# slider_V01.net
KiCad netlist of a schematic drawn in Altium Designer
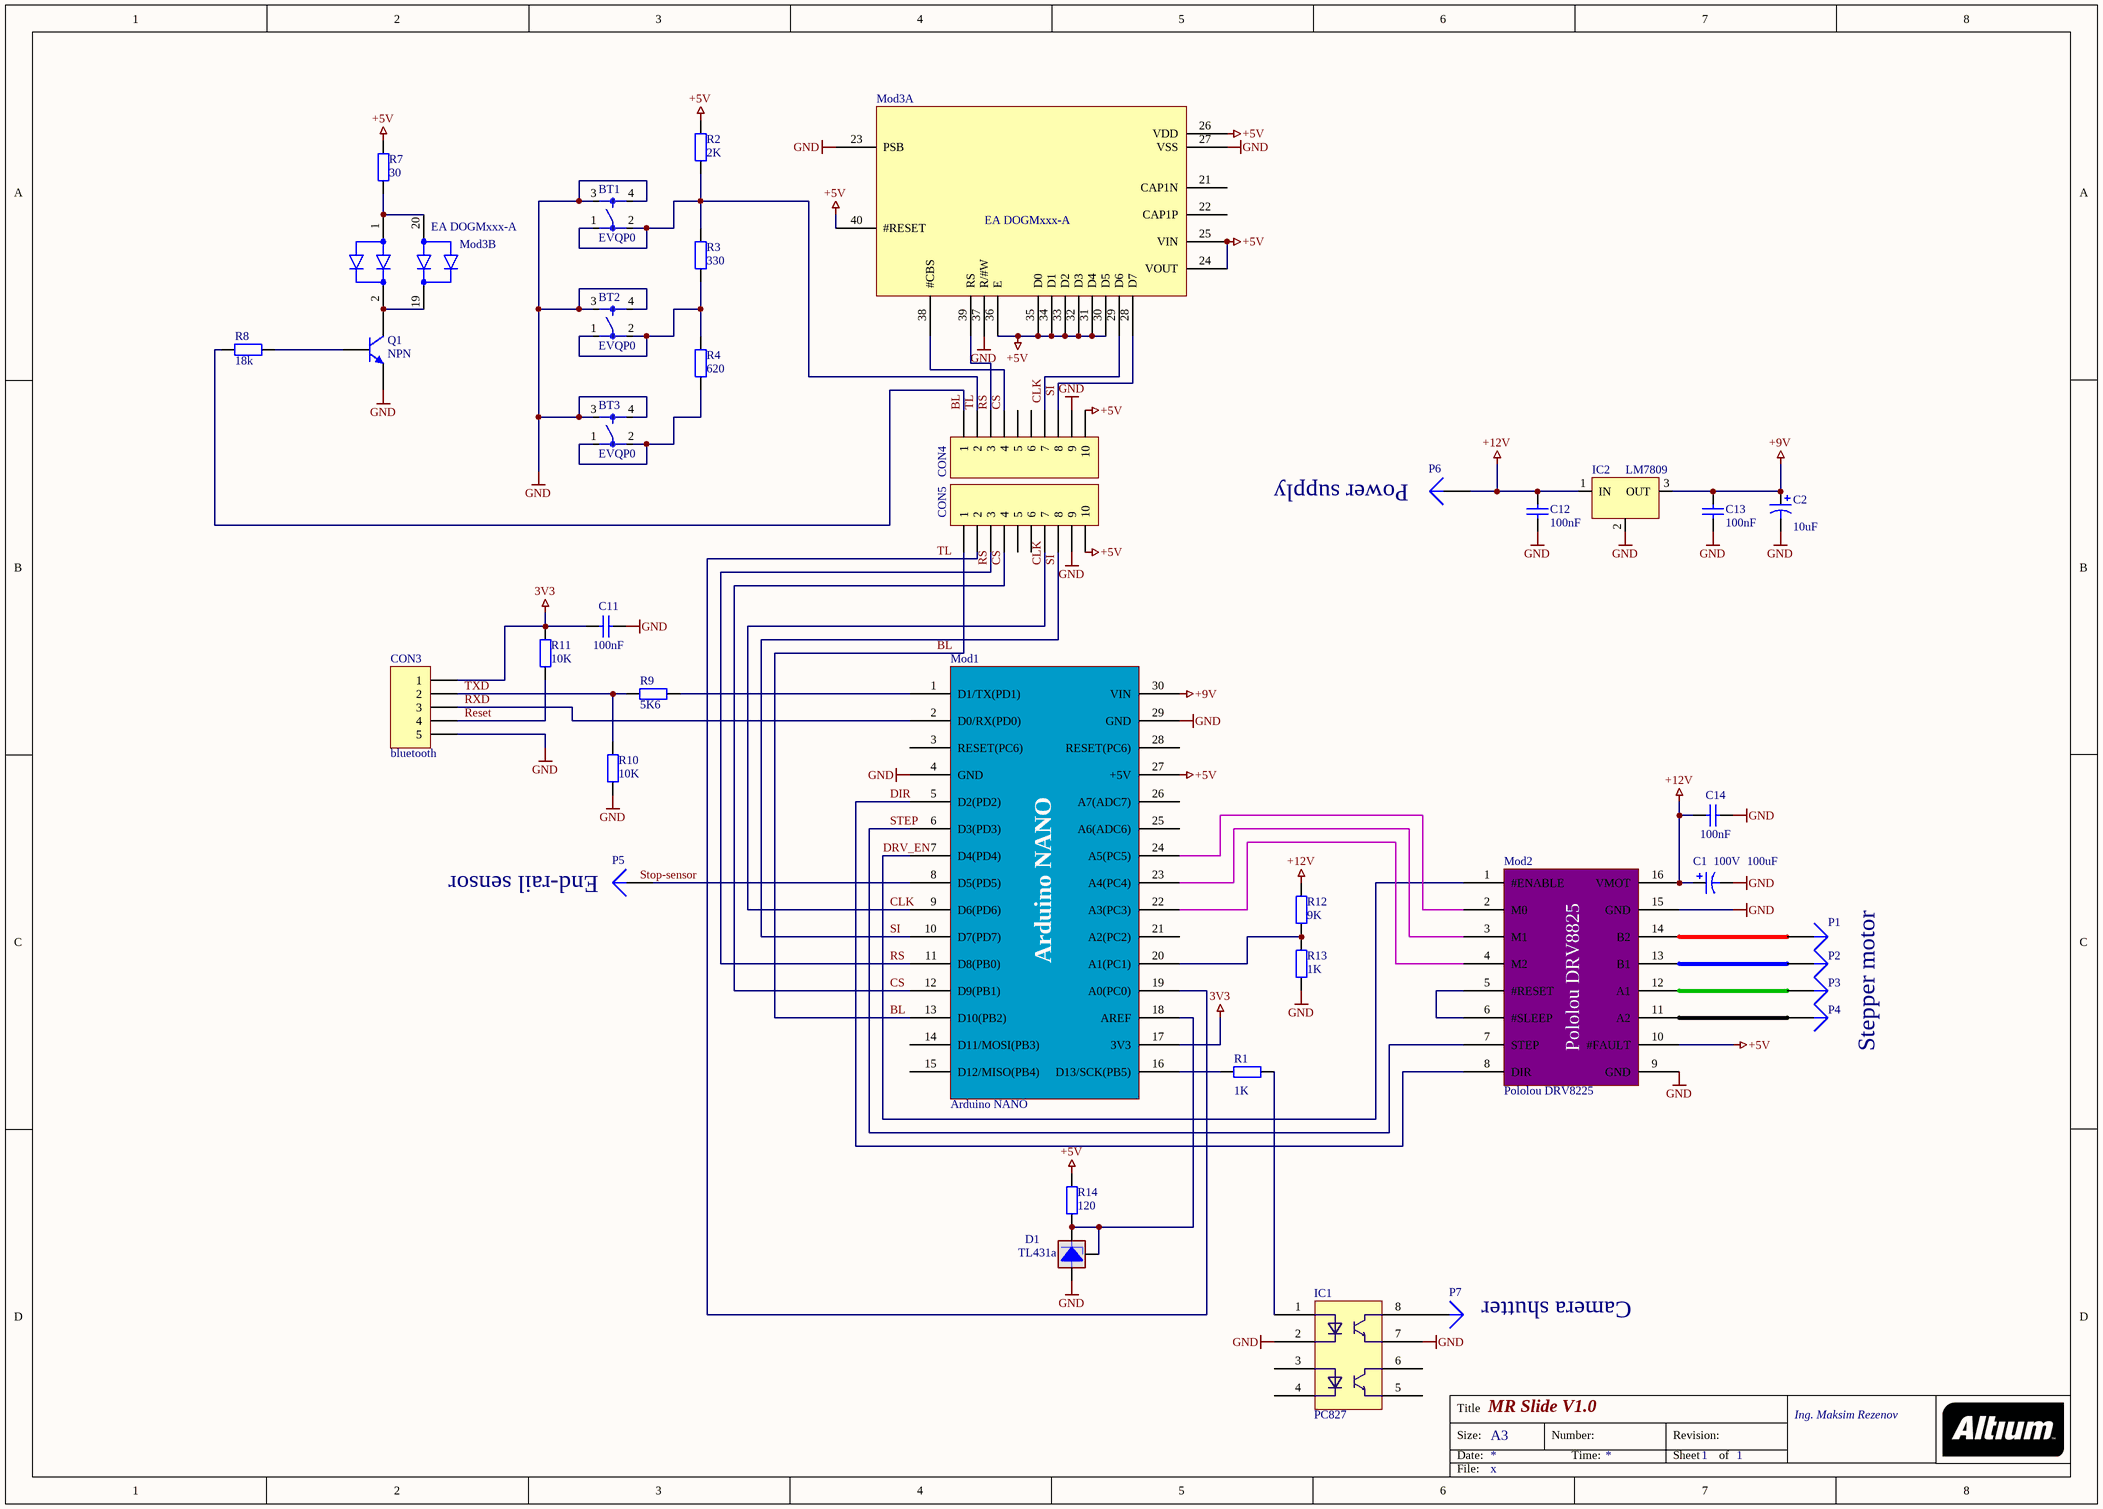
[diagram p0: slider_V01.SchDoc]

(export (version "E")
  (design (tool "Eeschema 10.0.6"))
  (components
    (comp (ref "BT1") (value "EVQP0") (footprint "EVQP0") (libsource (lib "new") (part "EVQP0")))
    (comp (ref "BT2") (value "EVQP0") (footprint "EVQP0") (libsource (lib "new") (part "EVQP0")))
    (comp (ref "BT3") (value "EVQP0") (footprint "EVQP0") (libsource (lib "new") (part "EVQP0")))
    (comp (ref "C1")
      (value "100V")
      (footprint "CAPR5-4X5")
      (description "Polarized Capacitor (Surface Mount)")
      (fields (field (name "ALTIUM_VALUE") "100uF") (field (name "PUBLISHER") "Altium Limited"))
      (libsource (lib "Miscellaneous Devices") (part "Cap Pol3"))
    )
    (comp (ref "C2")
      (value "10uF")
      (footprint "1812")
      (description "Polarized Capacitor (Surface Mount)")
      (fields (field (name "Comment") "Cap Pol3") (field (name "PUBLISHER") "Altium Limited"))
      (libsource (lib "Miscellaneous Devices") (part "Cap Pol3"))
    )
    (comp (ref "C11")
      (value "100nF")
      (footprint "C1206")
      (description "Capacitor (Semiconductor SIM Model)")
      (fields (field (name "Comment") "Cap Semi") (field (name "PUBLISHER") "Altium Limited"))
      (libsource (lib "Miscellaneous Devices") (part "Cap Semi"))
    )
    (comp (ref "C12")
      (value "100nF")
      (footprint "C1206")
      (description "Capacitor (Semiconductor SIM Model)")
      (fields (field (name "Comment") "Cap Semi") (field (name "PUBLISHER") "Altium Limited"))
      (libsource (lib "Miscellaneous Devices") (part "Cap Semi"))
    )
    (comp (ref "C13")
      (value "100nF")
      (footprint "C1206")
      (description "Capacitor (Semiconductor SIM Model)")
      (fields (field (name "Comment") "Cap Semi") (field (name "PUBLISHER") "Altium Limited"))
      (libsource (lib "Miscellaneous Devices") (part "Cap Semi"))
    )
    (comp (ref "C14")
      (value "100nF")
      (footprint "C1206")
      (description "Capacitor (Semiconductor SIM Model)")
      (fields (field (name "Comment") "Cap Semi") (field (name "PUBLISHER") "Altium Limited"))
      (libsource (lib "Miscellaneous Devices") (part "Cap Semi"))
    )
    (comp (ref "CON3")
      (value "bluetooth")
      (footprint "HDR1X5")
      (description "Header, 5-Pin")
      (fields (field (name "PUBLISHER") "Altium Limited"))
      (libsource (lib "Miscellaneous Connectors") (part "Header 5"))
    )
    (comp (ref "CON4")
      (value "Header 10")
      (footprint "HDR1X10")
      (description "Header, 10-Pin")
      (fields (field (name "PUBLISHER") "Altium Limited"))
      (libsource (lib "") (part "Header 10_1"))
    )
    (comp (ref "CON5")
      (value "Header 10")
      (footprint "HDR1X10")
      (description "Header, 10-Pin")
      (fields (field (name "PUBLISHER") "Altium Limited"))
      (libsource (lib "Miscellaneous Connectors") (part "Header 10"))
    )
    (comp (ref "D1")
      (value "TL431a")
      (footprint "SOT23-3")
      (libsource (lib "AAA-ACER_Library") (part "TL431a"))
    )
    (comp (ref "IC1") (value "PC827") (footprint "DIP-8") (libsource (lib "new") (part "PC827")))
    (comp (ref "IC2") (value "LM7809") (footprint "SOT89M") (libsource (lib "new") (part "LM780x")))
    (comp (ref "Mod1")
      (value "Arduino NANO")
      (footprint "arduino nano")
      (libsource (lib "new") (part "Arduino NANO"))
    )
    (comp (ref "Mod2")
      (value "Pololou DRV8225")
      (footprint "Pololou DRV8225")
      (libsource (lib "new") (part "Pololou DRV8225"))
    )
    (comp (ref "Mod3")
      (value "EA DOGMxxx-A")
      (footprint "EA DOGMxxx-A")
      (libsource (lib "new") (part "EA DOGMxxx-A"))
    )
    (comp (ref "P1")
      (value "Plug")
      (footprint "PIN1")
      (fields (field (name "PUBLISHER") "Altium Limited"))
      (libsource (lib "Miscellaneous Connectors") (part "Plug"))
    )
    (comp (ref "P2")
      (value "Plug")
      (footprint "PIN1")
      (fields (field (name "PUBLISHER") "Altium Limited"))
      (libsource (lib "Miscellaneous Connectors") (part "Plug"))
    )
    (comp (ref "P3")
      (value "Plug")
      (footprint "PIN1")
      (fields (field (name "PUBLISHER") "Altium Limited"))
      (libsource (lib "Miscellaneous Connectors") (part "Plug"))
    )
    (comp (ref "P4")
      (value "Plug")
      (footprint "PIN1")
      (fields (field (name "PUBLISHER") "Altium Limited"))
      (libsource (lib "Miscellaneous Connectors") (part "Plug"))
    )
    (comp (ref "P5")
      (value "Plug")
      (footprint "PIN1")
      (fields (field (name "PUBLISHER") "Altium Limited"))
      (libsource (lib "Miscellaneous Connectors") (part "Plug"))
    )
    (comp (ref "P6")
      (value "Plug")
      (footprint "PIN1")
      (fields (field (name "PUBLISHER") "Altium Limited"))
      (libsource (lib "Miscellaneous Connectors") (part "Plug"))
    )
    (comp (ref "P7")
      (value "Plug")
      (footprint "PIN1")
      (fields (field (name "PUBLISHER") "Altium Limited"))
      (libsource (lib "Miscellaneous Connectors") (part "Plug"))
    )
    (comp (ref "Q1")
      (value "NPN")
      (footprint "SOT23_N")
      (description "NPN Bipolar Transistor")
      (fields (field (name "PUBLISHER") "Altium Limited"))
      (libsource (lib "Miscellaneous Devices") (part "NPN"))
    )
    (comp (ref "R1")
      (value "1K")
      (footprint "C1206")
      (description "Resistor")
      (fields (field (name "Comment") "Res2") (field (name "PUBLISHER") "Altium Limited"))
      (libsource (lib "") (part "Res2_1"))
    )
    (comp (ref "R2")
      (value "2K")
      (footprint "C1206")
      (description "Resistor")
      (fields (field (name "Comment") "Res2") (field (name "PUBLISHER") "Altium Limited"))
      (libsource (lib "Miscellaneous Devices") (part "Res2"))
    )
    (comp (ref "R3")
      (value "330")
      (footprint "C1206")
      (description "Resistor")
      (fields (field (name "Comment") "Res2") (field (name "PUBLISHER") "Altium Limited"))
      (libsource (lib "Miscellaneous Devices") (part "Res2"))
    )
    (comp (ref "R4")
      (value "620")
      (footprint "C1206")
      (description "Resistor")
      (fields (field (name "Comment") "Res2") (field (name "PUBLISHER") "Altium Limited"))
      (libsource (lib "Miscellaneous Devices") (part "Res2"))
    )
    (comp (ref "R7")
      (value "30")
      (footprint "C1206")
      (description "Resistor")
      (fields (field (name "Comment") "Res2") (field (name "PUBLISHER") "Altium Limited"))
      (libsource (lib "Miscellaneous Devices") (part "Res2"))
    )
    (comp (ref "R8")
      (value "18k")
      (footprint "C1206")
      (description "Resistor")
      (fields (field (name "Comment") "Res2") (field (name "PUBLISHER") "Altium Limited"))
      (libsource (lib "") (part "Res2_2"))
    )
    (comp (ref "R9")
      (value "5K6")
      (footprint "C1206")
      (description "Resistor")
      (fields (field (name "Comment") "Res2") (field (name "PUBLISHER") "Altium Limited"))
      (libsource (lib "") (part "Res2_1"))
    )
    (comp (ref "R10")
      (value "10K")
      (footprint "C1206")
      (description "Resistor")
      (fields (field (name "Comment") "Res2") (field (name "PUBLISHER") "Altium Limited"))
      (libsource (lib "Miscellaneous Devices") (part "Res2"))
    )
    (comp (ref "R11")
      (value "10K")
      (footprint "C1206")
      (description "Resistor")
      (fields (field (name "Comment") "Res2") (field (name "PUBLISHER") "Altium Limited"))
      (libsource (lib "Miscellaneous Devices") (part "Res2"))
    )
    (comp (ref "R12")
      (value "9K")
      (footprint "C1206")
      (description "Resistor")
      (fields (field (name "Comment") "Res2") (field (name "PUBLISHER") "Altium Limited"))
      (libsource (lib "Miscellaneous Devices") (part "Res2"))
    )
    (comp (ref "R13")
      (value "1K")
      (footprint "C1206")
      (description "Resistor")
      (fields (field (name "Comment") "Res2") (field (name "PUBLISHER") "Altium Limited"))
      (libsource (lib "Miscellaneous Devices") (part "Res2"))
    )
    (comp (ref "R14")
      (value "120")
      (footprint "C1206")
      (description "Resistor")
      (fields (field (name "Comment") "Res2") (field (name "PUBLISHER") "Altium Limited"))
      (libsource (lib "Miscellaneous Devices") (part "Res2"))
    )
  )
  (nets
    (net (code "1") (name "+5V") (class "Default")
      (node (ref "CON4") (pin "10") (pinfunction "10_10") (pintype "passive"))
      (node (ref "CON5") (pin "10") (pinfunction "10_10") (pintype "passive"))
      (node (ref "Mod1") (pin "27") (pinfunction "+5V_27") (pintype "passive"))
      (node (ref "Mod2") (pin "10") (pinfunction "#FAULT_10") (pintype "passive"))
      (node (ref "Mod3") (pin "24") (pinfunction "VOUT_24") (pintype "passive"))
      (node (ref "Mod3") (pin "25") (pinfunction "VIN_25") (pintype "passive"))
      (node (ref "Mod3") (pin "26") (pinfunction "VDD_26") (pintype "passive"))
      (node (ref "Mod3") (pin "30") (pinfunction "D5_30") (pintype "passive"))
      (node (ref "Mod3") (pin "31") (pinfunction "D4_31") (pintype "passive"))
      (node (ref "Mod3") (pin "32") (pinfunction "D3_32") (pintype "passive"))
      (node (ref "Mod3") (pin "33") (pinfunction "D2_33") (pintype "passive"))
      (node (ref "Mod3") (pin "34") (pinfunction "D1_34") (pintype "passive"))
      (node (ref "Mod3") (pin "35") (pinfunction "D0_35") (pintype "passive"))
      (node (ref "Mod3") (pin "36") (pinfunction "E_36") (pintype "passive"))
      (node (ref "Mod3") (pin "40") (pinfunction "#RESET_40") (pintype "passive"))
      (node (ref "R14") (pin "2") (pinfunction "2_2") (pintype "passive"))
      (node (ref "R2") (pin "2") (pinfunction "2_2") (pintype "passive"))
      (node (ref "R7") (pin "2") (pinfunction "2_2") (pintype "passive"))
    )
    (net (code "2") (name "+9V") (class "Default")
      (node (ref "C13") (pin "2") (pinfunction "2_2") (pintype "passive"))
      (node (ref "C2") (pin "1") (pinfunction "1_1") (pintype "passive"))
      (node (ref "IC2") (pin "3") (pinfunction "OUT_3") (pintype "passive"))
      (node (ref "Mod1") (pin "30") (pinfunction "VIN_30") (pintype "passive"))
    )
    (net (code "3") (name "+12V") (class "Default")
      (node (ref "C1") (pin "1") (pinfunction "1_1") (pintype "passive"))
      (node (ref "C12") (pin "2") (pinfunction "2_2") (pintype "passive"))
      (node (ref "C14") (pin "1") (pinfunction "1_1") (pintype "passive"))
      (node (ref "IC2") (pin "1") (pinfunction "IN_1") (pintype "passive"))
      (node (ref "Mod2") (pin "16") (pinfunction "VMOT_16") (pintype "passive"))
      (node (ref "P6") (pin "1") (pinfunction "1_1") (pintype "passive"))
      (node (ref "R12") (pin "2") (pinfunction "2_2") (pintype "passive"))
    )
    (net (code "4") (name "/BL") (class "Default")
      (node (ref "CON4") (pin "1") (pinfunction "1_1") (pintype "passive"))
      (node (ref "CON5") (pin "1") (pinfunction "1_1") (pintype "passive"))
      (node (ref "Mod1") (pin "13") (pinfunction "D10(PB2)_13") (pintype "passive"))
      (node (ref "R8") (pin "2") (pinfunction "2_2") (pintype "passive"))
    )
    (net (code "5") (name "/CLK") (class "Default")
      (node (ref "CON4") (pin "7") (pinfunction "7_7") (pintype "passive"))
      (node (ref "CON5") (pin "7") (pinfunction "7_7") (pintype "passive"))
      (node (ref "Mod1") (pin "9") (pinfunction "D6(PD6)_9") (pintype "passive"))
      (node (ref "Mod3") (pin "29") (pinfunction "D6_29") (pintype "passive"))
    )
    (net (code "6") (name "/CS") (class "Default")
      (node (ref "CON4") (pin "4") (pinfunction "4_4") (pintype "passive"))
      (node (ref "CON5") (pin "4") (pinfunction "4_4") (pintype "passive"))
      (node (ref "Mod1") (pin "12") (pinfunction "D9(PB1)_12") (pintype "passive"))
      (node (ref "Mod3") (pin "38") (pinfunction "#CBS_38") (pintype "passive"))
    )
    (net (code "7") (name "/DIR") (class "Default")
      (node (ref "Mod1") (pin "5") (pinfunction "D2(PD2)_5") (pintype "passive"))
      (node (ref "Mod2") (pin "8") (pinfunction "DIR_8") (pintype "passive"))
    )
    (net (code "8") (name "/DRV_EN") (class "Default")
      (node (ref "Mod1") (pin "7") (pinfunction "D4(PD4)_7") (pintype "passive"))
      (node (ref "Mod2") (pin "1") (pinfunction "#ENABLE_1") (pintype "passive"))
    )
    (net (code "9") (name "/RS") (class "Default")
      (node (ref "CON4") (pin "3") (pinfunction "3_3") (pintype "passive"))
      (node (ref "CON5") (pin "3") (pinfunction "3_3") (pintype "passive"))
      (node (ref "Mod1") (pin "11") (pinfunction "D8(PB0)_11") (pintype "passive"))
      (node (ref "Mod3") (pin "39") (pinfunction "RS_39") (pintype "passive"))
    )
    (net (code "10") (name "/RXD") (class "Default")
      (node (ref "CON3") (pin "3") (pinfunction "3_3") (pintype "passive"))
      (node (ref "Mod1") (pin "2") (pinfunction "D0/RX(PD0)_2") (pintype "passive"))
    )
    (net (code "11") (name "/Reset") (class "Default")
      (node (ref "CON3") (pin "4") (pinfunction "4_4") (pintype "passive"))
      (node (ref "R11") (pin "1") (pinfunction "1_1") (pintype "passive"))
    )
    (net (code "12") (name "/SI") (class "Default")
      (node (ref "CON4") (pin "8") (pinfunction "8_8") (pintype "passive"))
      (node (ref "CON5") (pin "8") (pinfunction "8_8") (pintype "passive"))
      (node (ref "Mod1") (pin "10") (pinfunction "D7(PD7)_10") (pintype "passive"))
      (node (ref "Mod3") (pin "28") (pinfunction "D7_28") (pintype "passive"))
    )
    (net (code "13") (name "/STEP") (class "Default")
      (node (ref "Mod1") (pin "6") (pinfunction "D3(PD3)_6") (pintype "passive"))
      (node (ref "Mod2") (pin "7") (pinfunction "STEP_7") (pintype "passive"))
    )
    (net (code "15") (name "/TL") (class "Default")
      (node (ref "BT1") (pin "1") (pinfunction "1_1") (pintype "passive"))
      (node (ref "BT1") (pin "2") (pinfunction "2_2") (pintype "passive"))
      (node (ref "CON4") (pin "2") (pinfunction "2_2") (pintype "passive"))
      (node (ref "CON5") (pin "2") (pinfunction "2_2") (pintype "passive"))
      (node (ref "Mod1") (pin "19") (pinfunction "A0(PC0)_19") (pintype "passive"))
      (node (ref "R2") (pin "1") (pinfunction "1_1") (pintype "passive"))
      (node (ref "R3") (pin "2") (pinfunction "2_2") (pintype "passive"))
    )
    (net (code "16") (name "/TXD") (class "Default")
      (node (ref "CON3") (pin "2") (pinfunction "2_2") (pintype "passive"))
      (node (ref "R10") (pin "2") (pinfunction "2_2") (pintype "passive"))
      (node (ref "R9") (pin "1") (pinfunction "1_1") (pintype "passive"))
    )
    (net (code "17") (name "3V3") (class "Default")
      (node (ref "C11") (pin "1") (pinfunction "1_1") (pintype "passive"))
      (node (ref "CON3") (pin "1") (pinfunction "1_1") (pintype "passive"))
      (node (ref "Mod1") (pin "17") (pinfunction "3V3_17") (pintype "passive"))
      (node (ref "R11") (pin "2") (pinfunction "2_2") (pintype "passive"))
    )
    (net (code "18") (name "GND") (class "Default")
      (node (ref "BT1") (pin "3") (pinfunction "3_3") (pintype "passive"))
      (node (ref "BT1") (pin "4") (pinfunction "4_4") (pintype "passive"))
      (node (ref "BT2") (pin "3") (pinfunction "3_3") (pintype "passive"))
      (node (ref "BT2") (pin "4") (pinfunction "4_4") (pintype "passive"))
      (node (ref "BT3") (pin "3") (pinfunction "3_3") (pintype "passive"))
      (node (ref "BT3") (pin "4") (pinfunction "4_4") (pintype "passive"))
      (node (ref "C1") (pin "2") (pinfunction "2_2") (pintype "passive"))
      (node (ref "C11") (pin "2") (pinfunction "2_2") (pintype "passive"))
      (node (ref "C12") (pin "1") (pinfunction "1_1") (pintype "passive"))
      (node (ref "C13") (pin "1") (pinfunction "1_1") (pintype "passive"))
      (node (ref "C14") (pin "2") (pinfunction "2_2") (pintype "passive"))
      (node (ref "C2") (pin "2") (pinfunction "2_2") (pintype "passive"))
      (node (ref "CON3") (pin "5") (pinfunction "5_5") (pintype "passive"))
      (node (ref "CON4") (pin "9") (pinfunction "9_9") (pintype "passive"))
      (node (ref "CON5") (pin "9") (pinfunction "9_9") (pintype "passive"))
      (node (ref "D1") (pin "3") (pinfunction "A_3") (pintype "passive"))
      (node (ref "IC1") (pin "2") (pinfunction "2_2") (pintype "passive"))
      (node (ref "IC1") (pin "7") (pinfunction "7_7") (pintype "passive"))
      (node (ref "IC2") (pin "2") (pinfunction "GND_2") (pintype "passive"))
      (node (ref "Mod1") (pin "29") (pinfunction "GND_29") (pintype "passive"))
      (node (ref "Mod1") (pin "4") (pinfunction "GND_4") (pintype "passive"))
      (node (ref "Mod2") (pin "15") (pinfunction "GND_15") (pintype "passive"))
      (node (ref "Mod2") (pin "9") (pinfunction "GND_9") (pintype "passive"))
      (node (ref "Mod3") (pin "23") (pinfunction "PSB_23") (pintype "passive"))
      (node (ref "Mod3") (pin "27") (pinfunction "VSS_27") (pintype "passive"))
      (node (ref "Mod3") (pin "37") (pinfunction "R/#W_37") (pintype "passive"))
      (node (ref "Q1") (pin "3") (pinfunction "E_3") (pintype "passive"))
      (node (ref "R10") (pin "1") (pinfunction "1_1") (pintype "passive"))
      (node (ref "R13") (pin "1") (pinfunction "1_1") (pintype "passive"))
    )
    (net (code "19") (name "Net-(BT2-Pad1)") (class "Default")
      (node (ref "BT2") (pin "1") (pinfunction "1_1") (pintype "passive"))
      (node (ref "BT2") (pin "2") (pinfunction "2_2") (pintype "passive"))
      (node (ref "R3") (pin "1") (pinfunction "1_1") (pintype "passive"))
      (node (ref "R4") (pin "2") (pinfunction "2_2") (pintype "passive"))
    )
    (net (code "20") (name "Net-(BT3-Pad1)") (class "Default")
      (node (ref "BT3") (pin "1") (pinfunction "1_1") (pintype "passive"))
      (node (ref "BT3") (pin "2") (pinfunction "2_2") (pintype "passive"))
      (node (ref "R4") (pin "1") (pinfunction "1_1") (pintype "passive"))
    )
    (net (code "21") (name "Net-(D1-C)") (class "Default")
      (node (ref "D1") (pin "1") (pinfunction "C_1") (pintype "passive"))
      (node (ref "D1") (pin "2") (pinfunction "R_2") (pintype "passive"))
      (node (ref "Mod1") (pin "18") (pinfunction "AREF_18") (pintype "passive"))
      (node (ref "R14") (pin "1") (pinfunction "1_1") (pintype "passive"))
    )
    (net (code "22") (name "Net-(IC1-Pad1)") (class "Default")
      (node (ref "IC1") (pin "1") (pinfunction "1_1") (pintype "passive"))
      (node (ref "R1") (pin "2") (pinfunction "2_2") (pintype "passive"))
    )
    (net (code "23") (name "Net-(IC1-Pad8)") (class "Default")
      (node (ref "IC1") (pin "8") (pinfunction "8_8") (pintype "passive"))
      (node (ref "P7") (pin "1") (pinfunction "1_1") (pintype "passive"))
    )
    (net (code "24") (name "Net-(Mod1-A1(PC1))") (class "Default")
      (node (ref "Mod1") (pin "20") (pinfunction "A1(PC1)_20") (pintype "passive"))
      (node (ref "R12") (pin "1") (pinfunction "1_1") (pintype "passive"))
      (node (ref "R13") (pin "2") (pinfunction "2_2") (pintype "passive"))
    )
    (net (code "25") (name "Net-(Mod1-A3(PC3))") (class "Default")
      (node (ref "Mod1") (pin "22") (pinfunction "A3(PC3)_22") (pintype "passive"))
      (node (ref "Mod2") (pin "4") (pinfunction "M2_4") (pintype "passive"))
    )
    (net (code "26") (name "Net-(Mod1-A4(PC4))") (class "Default")
      (node (ref "Mod1") (pin "23") (pinfunction "A4(PC4)_23") (pintype "passive"))
      (node (ref "Mod2") (pin "3") (pinfunction "M1_3") (pintype "passive"))
    )
    (net (code "27") (name "Net-(Mod1-A5(PC5))") (class "Default")
      (node (ref "Mod1") (pin "24") (pinfunction "A5(PC5)_24") (pintype "passive"))
      (node (ref "Mod2") (pin "2") (pinfunction "M0_2") (pintype "passive"))
    )
    (net (code "28") (name "Net-(Mod1-D1{slash}TX(PD1))") (class "Default")
      (node (ref "Mod1") (pin "1") (pinfunction "D1/TX(PD1)_1") (pintype "passive"))
      (node (ref "R9") (pin "2") (pinfunction "2_2") (pintype "passive"))
    )
    (net (code "29") (name "Net-(Mod1-D5(PD5))") (class "Default")
      (node (ref "Mod1") (pin "8") (pinfunction "D5(PD5)_8") (pintype "passive"))
      (node (ref "P5") (pin "1") (pinfunction "1_1") (pintype "passive"))
    )
    (net (code "30") (name "Net-(Mod1-D13{slash}SCK(PB5))") (class "Default")
      (node (ref "Mod1") (pin "16") (pinfunction "D13/SCK(PB5)_16") (pintype "passive"))
      (node (ref "R1") (pin "1") (pinfunction "1_1") (pintype "passive"))
    )
    (net (code "31") (name "Net-(Mod2-#RESET)") (class "Default")
      (node (ref "Mod2") (pin "5") (pinfunction "#RESET_5") (pintype "passive"))
      (node (ref "Mod2") (pin "6") (pinfunction "#SLEEP_6") (pintype "passive"))
    )
    (net (code "32") (name "Net-(Mod2-A1)") (class "Default")
      (node (ref "Mod2") (pin "12") (pinfunction "A1_12") (pintype "passive"))
      (node (ref "P3") (pin "1") (pinfunction "1_1") (pintype "passive"))
    )
    (net (code "33") (name "Net-(Mod2-A2)") (class "Default")
      (node (ref "Mod2") (pin "11") (pinfunction "A2_11") (pintype "passive"))
      (node (ref "P4") (pin "1") (pinfunction "1_1") (pintype "passive"))
    )
    (net (code "34") (name "Net-(Mod2-B1)") (class "Default")
      (node (ref "Mod2") (pin "13") (pinfunction "B1_13") (pintype "passive"))
      (node (ref "P2") (pin "1") (pinfunction "1_1") (pintype "passive"))
    )
    (net (code "35") (name "Net-(Mod2-B2)") (class "Default")
      (node (ref "Mod2") (pin "14") (pinfunction "B2_14") (pintype "passive"))
      (node (ref "P1") (pin "1") (pinfunction "1_1") (pintype "passive"))
    )
    (net (code "36") (name "Net-(Mod3B-A1)") (class "Default")
      (node (ref "Mod3") (pin "1") (pinfunction "A1_1") (pintype "passive"))
      (node (ref "Mod3") (pin "20") (pinfunction "20_20") (pintype "passive"))
      (node (ref "R7") (pin "1") (pinfunction "1_1") (pintype "passive"))
    )
    (net (code "37") (name "Net-(Q1-B)") (class "Default")
      (node (ref "Q1") (pin "2") (pinfunction "B_2") (pintype "passive"))
      (node (ref "R8") (pin "1") (pinfunction "1_1") (pintype "passive"))
    )
    (net (code "38") (name "Net-(Q1-C)") (class "Default")
      (node (ref "Mod3") (pin "19") (pinfunction "19_19") (pintype "passive"))
      (node (ref "Mod3") (pin "2") (pinfunction "2_2") (pintype "passive"))
      (node (ref "Q1") (pin "1") (pinfunction "C_1") (pintype "passive"))
    )
    (net (code "39") (name "unconnected-(CON4-Pad5)") (class "Default")
      (node (ref "CON4") (pin "5") (pinfunction "5_5") (pintype "passive"))
    )
    (net (code "40") (name "unconnected-(CON4-Pad6)") (class "Default")
      (node (ref "CON4") (pin "6") (pinfunction "6_6") (pintype "passive"))
    )
    (net (code "41") (name "unconnected-(CON5-Pad5)") (class "Default")
      (node (ref "CON5") (pin "5") (pinfunction "5_5") (pintype "passive"))
    )
    (net (code "42") (name "unconnected-(CON5-Pad6)") (class "Default")
      (node (ref "CON5") (pin "6") (pinfunction "6_6") (pintype "passive"))
    )
    (net (code "43") (name "unconnected-(IC1-Pad3)") (class "Default")
      (node (ref "IC1") (pin "3") (pinfunction "3_3") (pintype "passive"))
    )
    (net (code "44") (name "unconnected-(IC1-Pad4)") (class "Default")
      (node (ref "IC1") (pin "4") (pinfunction "4_4") (pintype "passive"))
    )
    (net (code "45") (name "unconnected-(IC1-Pad5)") (class "Default")
      (node (ref "IC1") (pin "5") (pinfunction "5_5") (pintype "passive"))
    )
    (net (code "46") (name "unconnected-(IC1-Pad6)") (class "Default")
      (node (ref "IC1") (pin "6") (pinfunction "6_6") (pintype "passive"))
    )
    (net (code "47") (name "unconnected-(Mod1-A2(PC2)-Pad21)") (class "Default")
      (node (ref "Mod1") (pin "21") (pinfunction "A2(PC2)_21") (pintype "passive"))
    )
    (net (code "48") (name "unconnected-(Mod1-A6(ADC6)-Pad25)") (class "Default")
      (node (ref "Mod1") (pin "25") (pinfunction "A6(ADC6)_25") (pintype "passive"))
    )
    (net (code "49") (name "unconnected-(Mod1-A7(ADC7)-Pad26)") (class "Default")
      (node (ref "Mod1") (pin "26") (pinfunction "A7(ADC7)_26") (pintype "passive"))
    )
    (net (code "50") (name "unconnected-(Mod1-D11{slash}MOSI(PB3)-Pad14)") (class "Default")
      (node (ref "Mod1") (pin "14") (pinfunction "D11/MOSI(PB3)_14") (pintype "passive"))
    )
    (net (code "51") (name "unconnected-(Mod1-D12{slash}MISO(PB4)-Pad15)") (class "Default")
      (node (ref "Mod1") (pin "15") (pinfunction "D12/MISO(PB4)_15") (pintype "passive"))
    )
    (net (code "52") (name "unconnected-(Mod1-RESET(PC6)-Pad3)") (class "Default")
      (node (ref "Mod1") (pin "3") (pinfunction "RESET(PC6)_3") (pintype "passive"))
    )
    (net (code "53") (name "unconnected-(Mod1-RESET(PC6)-Pad28)") (class "Default")
      (node (ref "Mod1") (pin "28") (pinfunction "RESET(PC6)_28") (pintype "passive"))
    )
    (net (code "54") (name "unconnected-(Mod3A-CAP1N-Pad21)") (class "Default")
      (node (ref "Mod3") (pin "21") (pinfunction "CAP1N_21") (pintype "passive"))
    )
    (net (code "55") (name "unconnected-(Mod3A-CAP1P-Pad22)") (class "Default")
      (node (ref "Mod3") (pin "22") (pinfunction "CAP1P_22") (pintype "passive"))
    )
  )
)
